# shinobi_battery.net
KiCad netlist of a schematic drawn in EAGLE
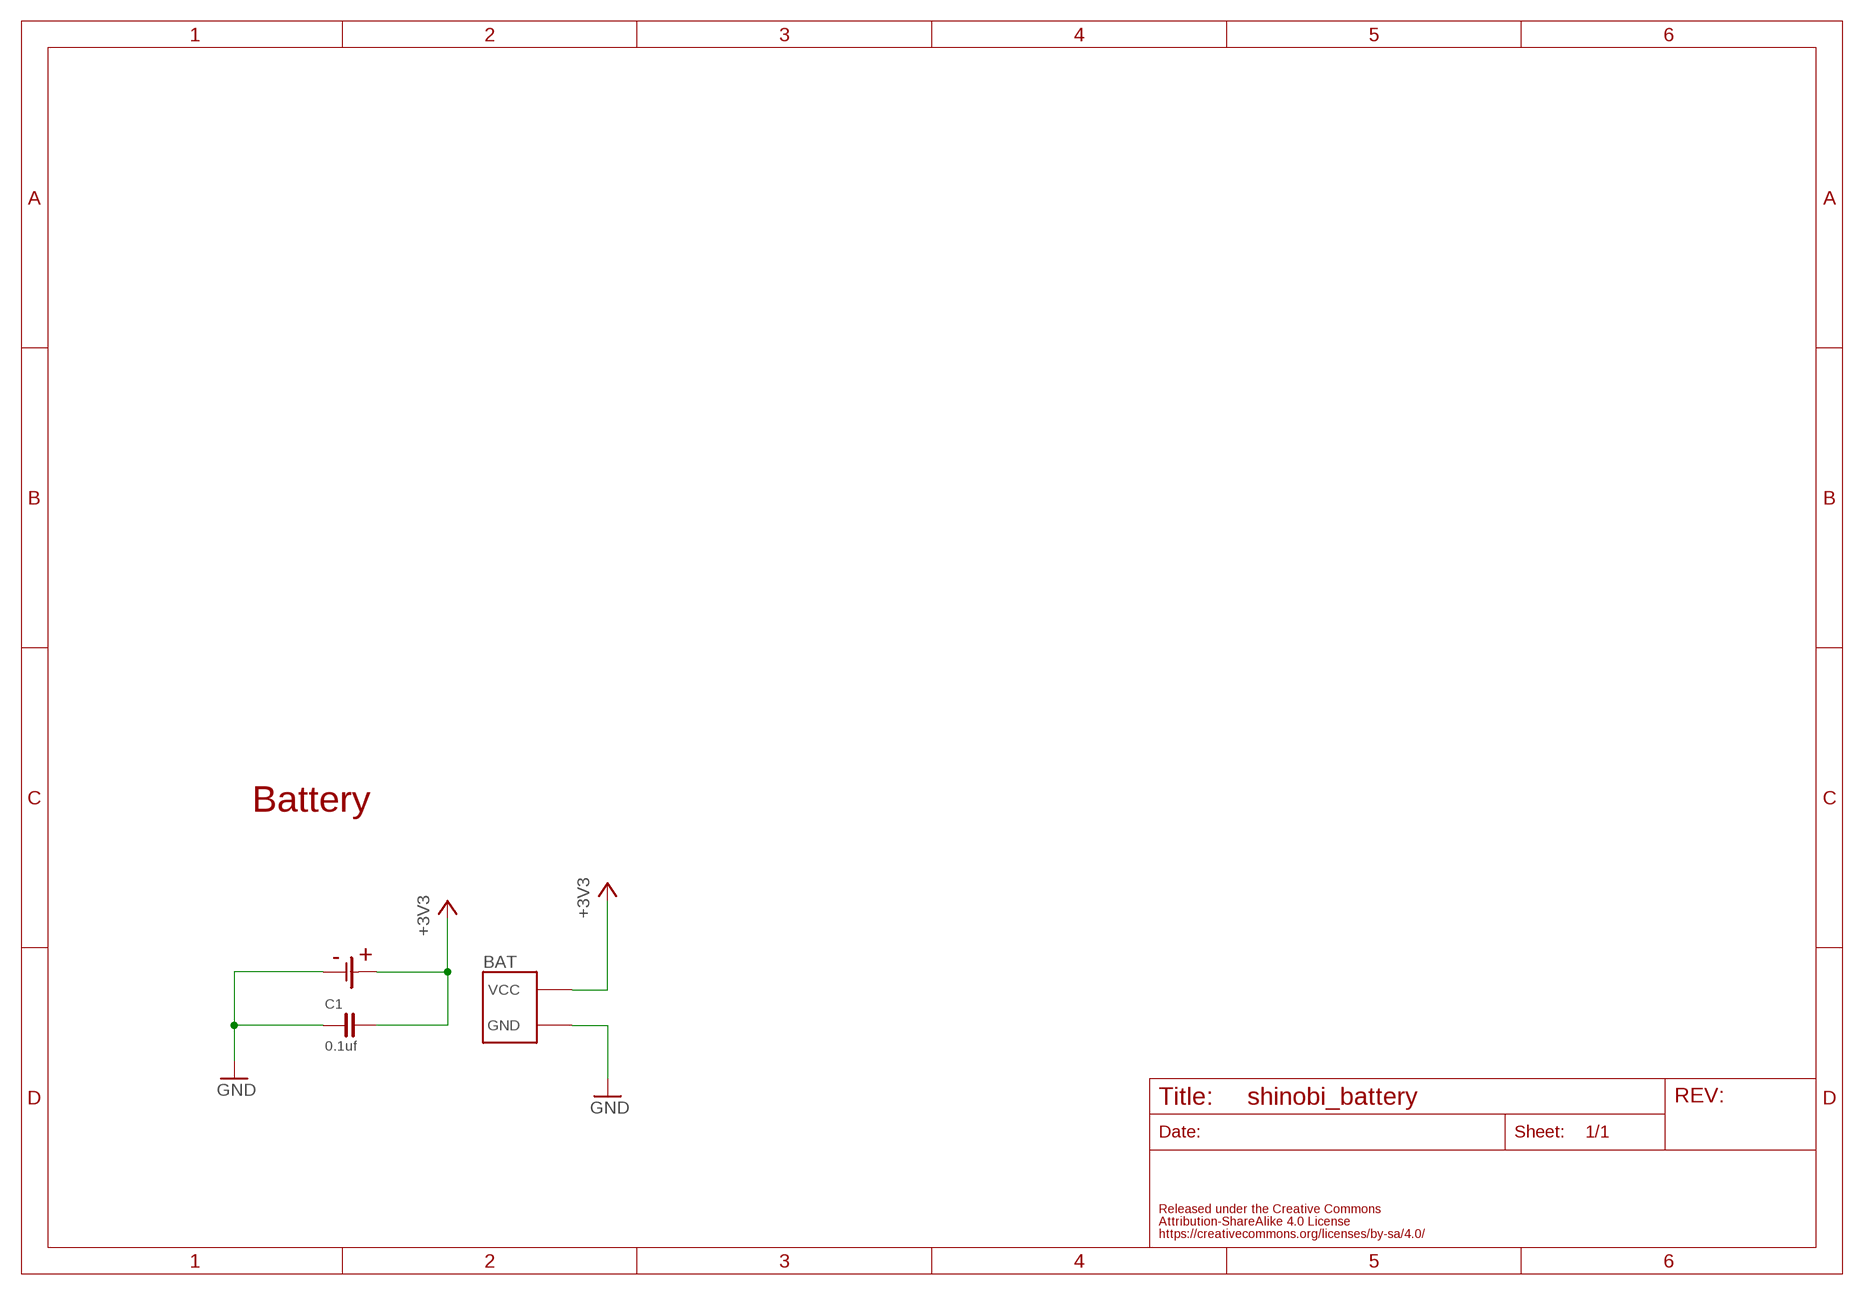
[diagram p0: schematic, sheet 1]

(export (version "E")
  (design (tool "Eeschema 10.0.6"))
  (components
    (comp (ref "BAT")
      (value "FABO_BRICK_2PIN_SIDE")
      (footprint "eagle-import:FABO_BRICK_2PIN_S02B−PASK-2_SILK")
      (libsource (lib "eagle-import") (part "FABO_BRICK_2PIN_SIDE"))
    )
    (comp (ref "C1")
      (value "0.1uf")
      (footprint "eagle-import:0603")
      (libsource (lib "eagle-import") (part "CAPACITOR-0603"))
    )
    (comp (ref "U$1")
      (value "CH031-2477FL")
      (footprint "eagle-import:CH031-2477FL")
      (libsource (lib "eagle-import") (part "CH031-2477FL"))
    )
  )
  (nets
    (net (code "1") (name "+3V3") (class "Default")
      (node (ref "BAT") (pin "VCC") (pinfunction "VCC_VCC") (pintype "bidirectional"))
      (node (ref "C1") (pin "2") (pinfunction "2_2") (pintype "passive"))
      (node (ref "U$1") (pin "+") (pinfunction "+_+") (pintype "bidirectional"))
    )
    (net (code "2") (name "GND") (class "Default")
      (node (ref "BAT") (pin "GND") (pinfunction "GND_GND") (pintype "bidirectional"))
      (node (ref "C1") (pin "1") (pinfunction "1_1") (pintype "passive"))
      (node (ref "U$1") (pin "-") (pinfunction "-_-") (pintype "bidirectional"))
    )
  )
)
